# OSO-RING-B1-00_never_fabbed.net
KiCad netlist of a schematic drawn in EAGLE
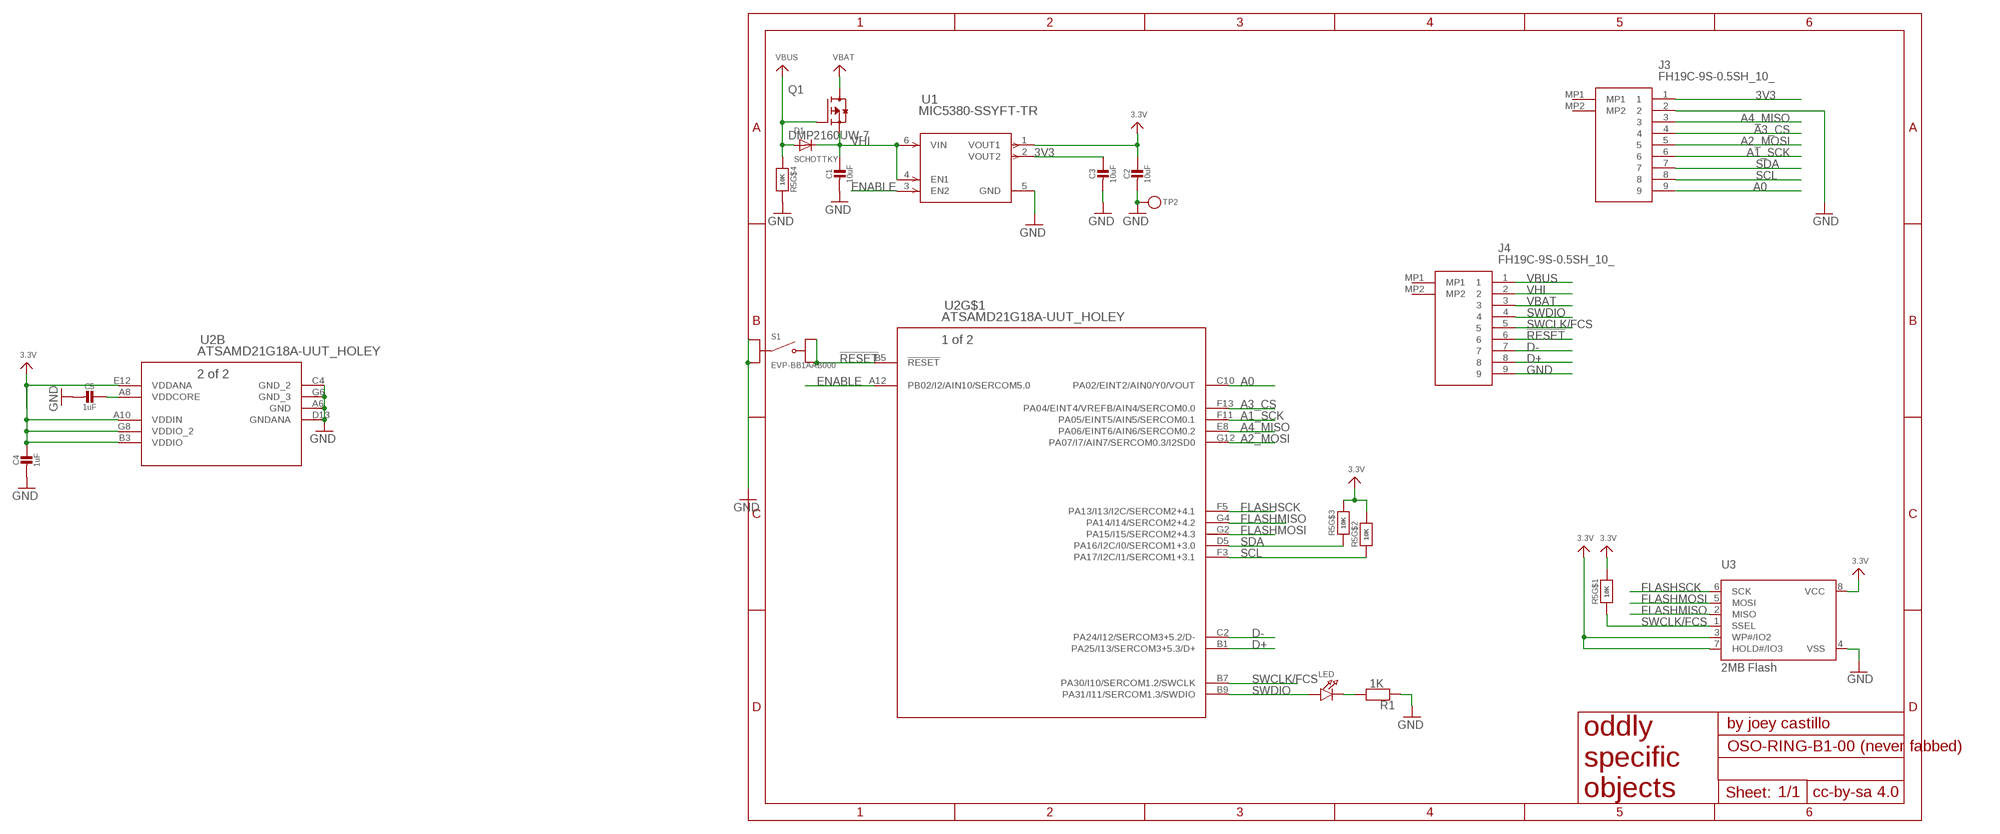
[diagram p0: schematic, sheet 1]

(export (version "E")
  (design (tool "Eeschema 10.0.6"))
  (components
    (comp (ref "C1")
      (value "10uF")
      (footprint "eagle-import:_0603MP")
      (libsource (lib "eagle-import") (part "CAP_CERAMIC_0603MP"))
    )
    (comp (ref "C2")
      (value "10uF")
      (footprint "eagle-import:_0603MP")
      (libsource (lib "eagle-import") (part "CAP_CERAMIC_0603MP"))
    )
    (comp (ref "C3")
      (value "10uF")
      (footprint "eagle-import:_0603MP")
      (libsource (lib "eagle-import") (part "CAP_CERAMIC_0603MP"))
    )
    (comp (ref "C4")
      (value "1uF")
      (footprint "eagle-import:_0603MP")
      (libsource (lib "eagle-import") (part "CAP_CERAMIC_0603MP"))
    )
    (comp (ref "C5")
      (value "1uF")
      (footprint "eagle-import:_0603MP")
      (libsource (lib "eagle-import") (part "CAP_CERAMIC_0603MP"))
    )
    (comp (ref "D1")
      (value "SCHOTTKY")
      (footprint "eagle-import:SOD-323F")
      (libsource (lib "eagle-import") (part "DIODESOD-323F"))
    )
    (comp (ref "J3")
      (value "FH19C-9S-0.5SH_10_")
      (footprint "eagle-import:FH19C9S05SH10")
      (fields
        (field (name "MANUFACTURER_PART_NUMBER") "FH19C-9S-0.5SH(10)")
        (field (name "MOUSER_PART_NUMBER") "798-FH19C9S05SH10")
      )
      (libsource (lib "eagle-import") (part "FH19C-9S-0.5SH_10_"))
    )
    (comp (ref "J4")
      (value "FH19C-9S-0.5SH_10_")
      (footprint "eagle-import:FH19C9S05SH10")
      (fields
        (field (name "MANUFACTURER_PART_NUMBER") "FH19C-9S-0.5SH(10)")
        (field (name "MOUSER_PART_NUMBER") "798-FH19C9S05SH10")
      )
      (libsource (lib "eagle-import") (part "FH19C-9S-0.5SH_10_"))
    )
    (comp (ref "LED")
      (value "LED0603_NOOUTLINE")
      (footprint "eagle-import:CHIPLED_0603_NOOUTLINE")
      (libsource (lib "eagle-import") (part "LED0603_NOOUTLINE"))
    )
    (comp (ref "Q1")
      (value "DMP2160UW-7")
      (footprint "eagle-import:SOT65P210X110-3N")
      (fields (field (name "DIGI-KEY_PART_NUMBER") "DMP2160UWDICT-ND") (field (name "MF") "Diodes Inc."))
      (libsource (lib "eagle-import") (part "DMP2160UW-7"))
    )
    (comp (ref "R1")
      (value "1K")
      (footprint "eagle-import:_0603MP")
      (libsource (lib "eagle-import") (part "RESISTOR_0603MP"))
    )
    (comp (ref "R5")
      (value "10K")
      (footprint "eagle-import:EXBV8V")
      (fields (field (name "MANUFACTURER_PART_NUMBER") "EXBV8V103JV"))
      (libsource (lib "eagle-import") (part "EXB-V8V103JV-GOOD"))
    )
    (comp (ref "S1")
      (value "EVP-BB1AAB000")
      (footprint "eagle-import:SW_EVP-BB1AAB000")
      (fields
        (field (name "DIGI-KEY_PART_NUMBER") "P124390CT-ND")
        (field (name "MF") "Panasonic Electronic Components")
      )
      (libsource (lib "eagle-import") (part "EVP-BB1AAB000"))
    )
    (comp (ref "TP2")
      (value "TESTPOINTPAD1MM")
      (footprint "eagle-import:TESTPOINT_PAD_1MM")
      (libsource (lib "eagle-import") (part "TESTPOINTPAD1MM"))
    )
    (comp (ref "U1")
      (value "MIC5380-SSYFT-TR")
      (footprint "eagle-import:TMLF-6_FT_MCH")
      (fields (field (name "COPYRIGHT") "Copyright (C) 2018 Accelerated Designs. All rights reserved"))
      (libsource (lib "eagle-import") (part "MIC5380-SSYFT-TR"))
    )
    (comp (ref "U2")
      (value "ATSAMD21G18A-UUT_HOLEY")
      (footprint "eagle-import:WLCSP45_2P6X2P9_HOLEY")
      (libsource (lib "eagle-import") (part "ATSAMD21G18A-UUT_HOLEY"))
    )
    (comp (ref "U3")
      (value "2MB Flash")
      (footprint "eagle-import:USON8")
      (libsource (lib "eagle-import") (part "SPIFLASH_8PINUX"))
    )
  )
  (nets
    (net (code "1") (name "/3V3") (class "Default")
      (node (ref "C3") (pin "1") (pinfunction "1_1") (pintype "passive"))
      (node (ref "J3") (pin "1") (pinfunction "1_1") (pintype "bidirectional"))
      (node (ref "U1") (pin "2") (pinfunction "VOUT2_2") (pintype "output"))
    )
    (net (code "2") (name "/A0") (class "Default")
      (node (ref "J3") (pin "9") (pinfunction "9_9") (pintype "bidirectional"))
      (node (ref "U2") (pin "C10") (pinfunction "PA02/EINT2/AIN0/Y0/VOUT_C10") (pintype "bidirectional"))
    )
    (net (code "3") (name "/A1_SCK") (class "Default")
      (node (ref "J3") (pin "6") (pinfunction "6_6") (pintype "bidirectional"))
      (node (ref "U2") (pin "F11") (pinfunction "PA05/EINT5/AIN5/SERCOM0.1_F11") (pintype "bidirectional"))
    )
    (net (code "4") (name "/A2_MOSI") (class "Default")
      (node (ref "J3") (pin "5") (pinfunction "5_5") (pintype "bidirectional"))
      (node (ref "U2") (pin "G12") (pinfunction "PA07/I7/AIN7/SERCOM0.3/I2SD0_G12") (pintype "bidirectional"))
    )
    (net (code "5") (name "/A3_CS") (class "Default")
      (node (ref "J3") (pin "4") (pinfunction "4_4") (pintype "bidirectional"))
      (node (ref "U2") (pin "F13") (pinfunction "PA04/EINT4/VREFB/AIN4/SERCOM0.0_F13") (pintype "bidirectional"))
    )
    (net (code "6") (name "/A4_MISO") (class "Default")
      (node (ref "J3") (pin "3") (pinfunction "3_3") (pintype "bidirectional"))
      (node (ref "U2") (pin "E8") (pinfunction "PA06/EINT6/AIN6/SERCOM0.2_E8") (pintype "bidirectional"))
    )
    (net (code "7") (name "/D+") (class "Default")
      (node (ref "J4") (pin "8") (pinfunction "8_8") (pintype "bidirectional"))
      (node (ref "U2") (pin "B1") (pinfunction "PA25/I13/SERCOM3+5.3/D+_B1") (pintype "bidirectional"))
    )
    (net (code "8") (name "/D-") (class "Default")
      (node (ref "J4") (pin "7") (pinfunction "7_7") (pintype "bidirectional"))
      (node (ref "U2") (pin "C2") (pinfunction "PA24/I12/SERCOM3+5.2/D-_C2") (pintype "bidirectional"))
    )
    (net (code "9") (name "/ENABLE") (class "Default")
      (node (ref "U1") (pin "3") (pinfunction "EN2_3") (pintype "input"))
      (node (ref "U2") (pin "A12") (pinfunction "PB02/I2/AIN10/SERCOM5.0_A12") (pintype "bidirectional"))
    )
    (net (code "10") (name "/FLASHMISO") (class "Default")
      (node (ref "U2") (pin "G4") (pinfunction "PA14/I14/SERCOM2+4.2_G4") (pintype "bidirectional"))
      (node (ref "U3") (pin "2") (pinfunction "MISO_2") (pintype "bidirectional"))
    )
    (net (code "11") (name "/FLASHMOSI") (class "Default")
      (node (ref "U2") (pin "G2") (pinfunction "PA15/I15/SERCOM2+4.3_G2") (pintype "bidirectional"))
      (node (ref "U3") (pin "5") (pinfunction "MOSI_5") (pintype "bidirectional"))
    )
    (net (code "12") (name "/FLASHSCK") (class "Default")
      (node (ref "U2") (pin "F5") (pinfunction "PA13/I13/I2C/SERCOM2+4.1_F5") (pintype "bidirectional"))
      (node (ref "U3") (pin "6") (pinfunction "SCK_6") (pintype "bidirectional"))
    )
    (net (code "13") (name "/SCL") (class "Default")
      (node (ref "J3") (pin "8") (pinfunction "8_8") (pintype "bidirectional"))
      (node (ref "R5") (pin "2") (pinfunction "1_2") (pintype "passive"))
      (node (ref "U2") (pin "F3") (pinfunction "PA17/I2C/I1/SERCOM1+3.1_F3") (pintype "bidirectional"))
    )
    (net (code "14") (name "/SDA") (class "Default")
      (node (ref "J3") (pin "7") (pinfunction "7_7") (pintype "bidirectional"))
      (node (ref "R5") (pin "3") (pinfunction "1_3") (pintype "passive"))
      (node (ref "U2") (pin "D5") (pinfunction "PA16/I2C/I0/SERCOM1+3.0_D5") (pintype "bidirectional"))
    )
    (net (code "15") (name "/SWCLK{slash}FCS") (class "Default")
      (node (ref "J4") (pin "5") (pinfunction "5_5") (pintype "bidirectional"))
      (node (ref "R5") (pin "1") (pinfunction "1_1") (pintype "passive"))
      (node (ref "U2") (pin "B7") (pinfunction "PA30/I10/SERCOM1.2/SWCLK_B7") (pintype "bidirectional"))
      (node (ref "U3") (pin "1") (pinfunction "SSEL_1") (pintype "bidirectional"))
    )
    (net (code "16") (name "/SWDIO") (class "Default")
      (node (ref "J4") (pin "4") (pinfunction "4_4") (pintype "bidirectional"))
      (node (ref "LED") (pin "A") (pinfunction "A_A") (pintype "passive"))
      (node (ref "U2") (pin "B9") (pinfunction "PA31/I11/SERCOM1.3/SWDIO_B9") (pintype "bidirectional"))
    )
    (net (code "17") (name "/VHI") (class "Default")
      (node (ref "C1") (pin "1") (pinfunction "1_1") (pintype "passive"))
      (node (ref "D1") (pin "C") (pinfunction "C_C") (pintype "passive"))
      (node (ref "J4") (pin "2") (pinfunction "2_2") (pintype "bidirectional"))
      (node (ref "Q1") (pin "2") (pinfunction "S_2") (pintype "passive"))
      (node (ref "U1") (pin "4") (pinfunction "EN1_4") (pintype "input"))
      (node (ref "U1") (pin "6") (pinfunction "VIN_6") (pintype "input"))
    )
    (net (code "18") (name "/~{RESET}") (class "Default")
      (node (ref "J4") (pin "6") (pinfunction "6_6") (pintype "bidirectional"))
      (node (ref "S1") (pin "B1") (pinfunction "B1_B1") (pintype "passive"))
      (node (ref "S1") (pin "B2") (pinfunction "B2_B2") (pintype "passive"))
      (node (ref "U2") (pin "B5") (pinfunction "~{RESET}_B5") (pintype "passive"))
    )
    (net (code "19") (name "3.3V") (class "Default")
      (node (ref "C2") (pin "1") (pinfunction "1_1") (pintype "passive"))
      (node (ref "C4") (pin "1") (pinfunction "1_1") (pintype "passive"))
      (node (ref "R5") (pin "6") (pinfunction "2_6") (pintype "passive"))
      (node (ref "R5") (pin "7") (pinfunction "2_7") (pintype "passive"))
      (node (ref "R5") (pin "8") (pinfunction "2_8") (pintype "passive"))
      (node (ref "U1") (pin "1") (pinfunction "VOUT1_1") (pintype "output"))
      (node (ref "U2") (pin "A10") (pinfunction "VDDIN_A10") (pintype "power_in"))
      (node (ref "U2") (pin "B3") (pinfunction "VDDIO_B3") (pintype "power_in"))
      (node (ref "U2") (pin "E12") (pinfunction "VDDANA_E12") (pintype "power_in"))
      (node (ref "U2") (pin "G8") (pinfunction "VDDIO_2_G8") (pintype "power_in"))
      (node (ref "U3") (pin "3") (pinfunction "WP#/IO2_3") (pintype "bidirectional"))
      (node (ref "U3") (pin "7") (pinfunction "HOLD#/IO3_7") (pintype "bidirectional"))
      (node (ref "U3") (pin "8") (pinfunction "VCC_8") (pintype "bidirectional"))
    )
    (net (code "20") (name "GND") (class "Default")
      (node (ref "C1") (pin "2") (pinfunction "2_2") (pintype "passive"))
      (node (ref "C2") (pin "2") (pinfunction "2_2") (pintype "passive"))
      (node (ref "C3") (pin "2") (pinfunction "2_2") (pintype "passive"))
      (node (ref "C4") (pin "2") (pinfunction "2_2") (pintype "passive"))
      (node (ref "C5") (pin "2") (pinfunction "2_2") (pintype "passive"))
      (node (ref "J3") (pin "2") (pinfunction "2_2") (pintype "bidirectional"))
      (node (ref "J4") (pin "9") (pinfunction "9_9") (pintype "bidirectional"))
      (node (ref "R1") (pin "1") (pinfunction "1_1") (pintype "passive"))
      (node (ref "R5") (pin "5") (pinfunction "2_5") (pintype "passive"))
      (node (ref "S1") (pin "A1") (pinfunction "A1_A1") (pintype "passive"))
      (node (ref "S1") (pin "A2") (pinfunction "A2_A2") (pintype "passive"))
      (node (ref "TP2") (pin "P$1") (pinfunction "P$1_P$1") (pintype "bidirectional"))
      (node (ref "U1") (pin "5") (pinfunction "GND_5") (pintype "power_in"))
      (node (ref "U2") (pin "A6") (pinfunction "GND_A6") (pintype "passive"))
      (node (ref "U2") (pin "C4") (pinfunction "GND_2_C4") (pintype "passive"))
      (node (ref "U2") (pin "D13") (pinfunction "GNDANA_D13") (pintype "passive"))
      (node (ref "U2") (pin "G6") (pinfunction "GND_3_G6") (pintype "passive"))
      (node (ref "U3") (pin "4") (pinfunction "VSS_4") (pintype "bidirectional"))
    )
    (net (code "21") (name "Net-(LED-PadC)") (class "Default")
      (node (ref "LED") (pin "C") (pinfunction "C_C") (pintype "passive"))
      (node (ref "R1") (pin "2") (pinfunction "2_2") (pintype "passive"))
    )
    (net (code "22") (name "Net-(U2A-VDDCORE)") (class "Default")
      (node (ref "C5") (pin "1") (pinfunction "1_1") (pintype "passive"))
      (node (ref "U2") (pin "A8") (pinfunction "VDDCORE_A8") (pintype "power_in"))
    )
    (net (code "23") (name "VBAT") (class "Default")
      (node (ref "J4") (pin "3") (pinfunction "3_3") (pintype "bidirectional"))
      (node (ref "Q1") (pin "3") (pinfunction "D_3") (pintype "passive"))
    )
    (net (code "24") (name "VBUS") (class "Default")
      (node (ref "D1") (pin "A") (pinfunction "A_A") (pintype "passive"))
      (node (ref "J4") (pin "1") (pinfunction "1_1") (pintype "bidirectional"))
      (node (ref "Q1") (pin "1") (pinfunction "G_1") (pintype "passive"))
      (node (ref "R5") (pin "4") (pinfunction "1_4") (pintype "passive"))
    )
    (net (code "25") (name "unconnected-(J3-PadMP1)") (class "Default")
      (node (ref "J3") (pin "MP1") (pinfunction "MP1_MP1") (pintype "bidirectional"))
    )
    (net (code "26") (name "unconnected-(J3-PadMP2)") (class "Default")
      (node (ref "J3") (pin "MP2") (pinfunction "MP2_MP2") (pintype "bidirectional"))
    )
    (net (code "27") (name "unconnected-(J4-PadMP1)") (class "Default")
      (node (ref "J4") (pin "MP1") (pinfunction "MP1_MP1") (pintype "bidirectional"))
    )
    (net (code "28") (name "unconnected-(J4-PadMP2)") (class "Default")
      (node (ref "J4") (pin "MP2") (pinfunction "MP2_MP2") (pintype "bidirectional"))
    )
  )
)
